# EBAZEXTV1.net
KiCad netlist of a schematic drawn in Altium Designer
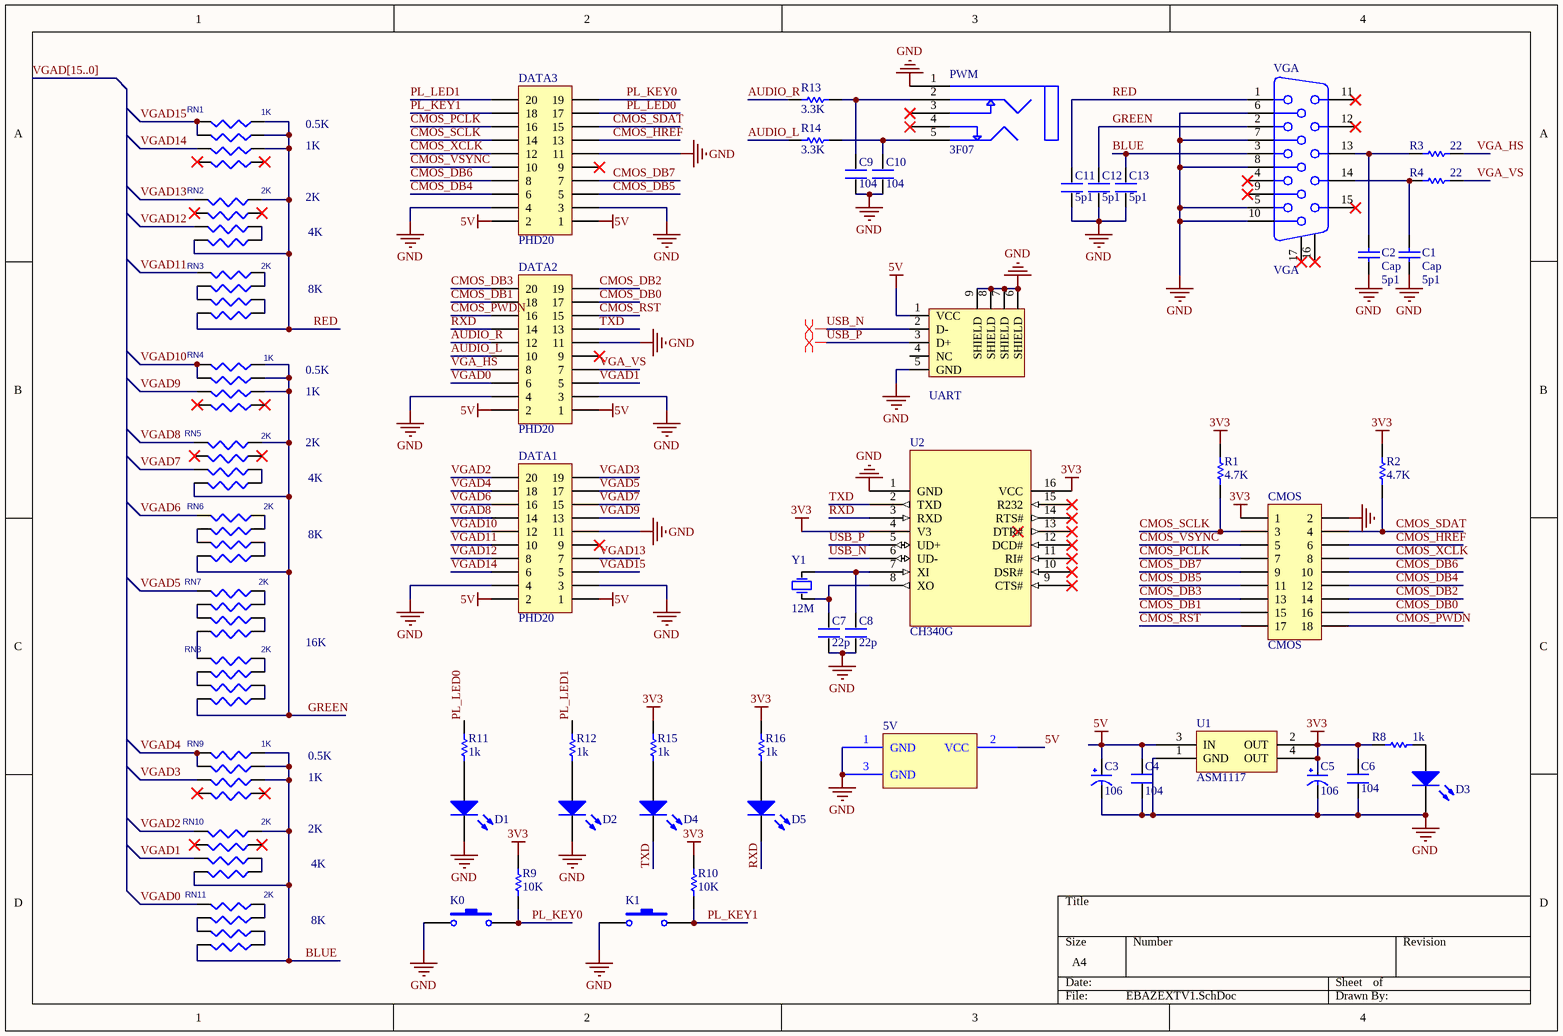
[diagram p0: EBAZEXTV1.SchDoc]

(export (version "E")
  (design (tool "Eeschema 10.0.6"))
  (components
    (comp (ref "5V")
      (value "DC005电源插座")
      (footprint "POWER_CON_max")
      (libsource (lib "FPGA+DSP") (part "POWER_CON"))
    )
    (comp (ref "C1")
      (value "Cap")
      (footprint "0805")
      (description "Capacitor")
      (fields (field (name "ALTIUM_VALUE") "5p1") (field (name "PUBLISHER") "Altium Limited"))
      (libsource (lib "Miscellaneous Devices") (part "Cap"))
    )
    (comp (ref "C2")
      (value "Cap")
      (footprint "0805")
      (description "Capacitor")
      (fields (field (name "ALTIUM_VALUE") "5p1") (field (name "PUBLISHER") "Altium Limited"))
      (libsource (lib "Miscellaneous Devices") (part "Cap"))
    )
    (comp (ref "C3") (value "106") (footprint "1206A") (libsource (lib "Explorer STM32F407封装库") (part "CAP")))
    (comp (ref "C4") (value "104") (footprint "0805") (libsource (lib "Explorer STM32F407封装库") (part "C_3")))
    (comp (ref "C5") (value "106") (footprint "1206A") (libsource (lib "Explorer STM32F407封装库") (part "CAP")))
    (comp (ref "C6") (value "104") (footprint "0805") (libsource (lib "Explorer STM32F407封装库") (part "C_3")))
    (comp (ref "C7") (value "22p") (footprint "0805") (libsource (lib "Explorer STM32F407封装库") (part "C_3")))
    (comp (ref "C8") (value "22p") (footprint "0805") (libsource (lib "Explorer STM32F407封装库") (part "C_3")))
    (comp (ref "C9") (value "104") (footprint "0805") (libsource (lib "Explorer STM32F407封装库") (part "C_3")))
    (comp (ref "C10") (value "104") (footprint "0805") (libsource (lib "Explorer STM32F407封装库") (part "C_3")))
    (comp (ref "C11") (value "5p1") (footprint "0805") (libsource (lib "Explorer STM32F407封装库") (part "C_3")))
    (comp (ref "C12") (value "5p1") (footprint "0805") (libsource (lib "Explorer STM32F407封装库") (part "C_3")))
    (comp (ref "C13") (value "5p1") (footprint "0805") (libsource (lib "Explorer STM32F407封装库") (part "C_3")))
    (comp (ref "CMOS")
      (value "CMOS")
      (footprint "HDR2X9")
      (description "Header, 9-Pin, Dual row")
      (fields (field (name "PUBLISHER") "Altium Limited"))
      (libsource (lib "Miscellaneous Connectors") (part "Header 9X2"))
    )
    (comp (ref "D1")
      (value "LED0")
      (footprint "LED-0805")
      (description "发光二极管")
      (fields (field (name "PUBLISHER") "Altium Limited"))
      (libsource (lib "fszhang") (part "LED0"))
    )
    (comp (ref "D2")
      (value "LED0")
      (footprint "LED-0805")
      (description "发光二极管")
      (fields (field (name "PUBLISHER") "Altium Limited"))
      (libsource (lib "fszhang") (part "LED0"))
    )
    (comp (ref "D3")
      (value "LED0")
      (footprint "LED-0805")
      (description "发光二极管")
      (fields (field (name "PUBLISHER") "Altium Limited"))
      (libsource (lib "fszhang") (part "LED0"))
    )
    (comp (ref "D4")
      (value "LED0")
      (footprint "LED-0805")
      (description "发光二极管")
      (fields (field (name "PUBLISHER") "Altium Limited"))
      (libsource (lib "fszhang") (part "LED0"))
    )
    (comp (ref "D5")
      (value "LED0")
      (footprint "LED-0805")
      (description "发光二极管")
      (fields (field (name "PUBLISHER") "Altium Limited"))
      (libsource (lib "fszhang") (part "LED0"))
    )
    (comp (ref "DATA1")
      (value "PHD20")
      (footprint "37")
      (description "Header, 10-Pin, Dual row")
      (fields (field (name "PUBLISHER") "Altium Limited"))
      (libsource (lib "Miscellaneous Connectors") (part "Header 10X2"))
    )
    (comp (ref "DATA2")
      (value "PHD20")
      (footprint "37")
      (description "Header, 10-Pin, Dual row")
      (fields (field (name "PUBLISHER") "Altium Limited"))
      (libsource (lib "Miscellaneous Connectors") (part "Header 10X2"))
    )
    (comp (ref "DATA3")
      (value "PHD20")
      (footprint "37")
      (description "Header, 10-Pin, Dual row")
      (fields (field (name "PUBLISHER") "Altium Limited"))
      (libsource (lib "Miscellaneous Connectors") (part "Header 10X2"))
    )
    (comp (ref "K0")
      (value "SW-PB")
      (footprint "key_2")
      (description "Switch")
      (fields (field (name "PUBLISHER") "Altium Limited"))
      (libsource (lib "Miscellaneous Devices") (part "SW-PB"))
    )
    (comp (ref "K1")
      (value "SW-PB")
      (footprint "key_2")
      (description "Switch")
      (fields (field (name "PUBLISHER") "Altium Limited"))
      (libsource (lib "Miscellaneous Devices") (part "SW-PB"))
    )
    (comp (ref "PWM")
      (value "3F07")
      (footprint "3F07")
      (description "立体声耳机插座")
      (libsource (lib "HDR_fszhang") (part "3F07"))
    )
    (comp (ref "R1")
      (value "4.7K")
      (footprint "R0805")
      (description "Resistor")
      (fields (field (name "PUBLISHER") "Altium Limited"))
      (libsource (lib "My Footprint") (part "RES"))
    )
    (comp (ref "R2")
      (value "4.7K")
      (footprint "R0805")
      (description "Resistor")
      (fields (field (name "PUBLISHER") "Altium Limited"))
      (libsource (lib "My Footprint") (part "RES"))
    )
    (comp (ref "R3")
      (value "22")
      (footprint "R0805")
      (description "Resistor")
      (fields (field (name "PUBLISHER") "Altium Limited"))
      (libsource (lib "My Footprint") (part "RES"))
    )
    (comp (ref "R4")
      (value "22")
      (footprint "R0805")
      (description "Resistor")
      (fields (field (name "PUBLISHER") "Altium Limited"))
      (libsource (lib "My Footprint") (part "RES"))
    )
    (comp (ref "R8")
      (value "1k")
      (footprint "R0805")
      (description "Resistor")
      (fields (field (name "PUBLISHER") "Altium Limited"))
      (libsource (lib "My Footprint") (part "RES"))
    )
    (comp (ref "R9")
      (value "10K")
      (footprint "R0805")
      (description "Resistor")
      (fields (field (name "PUBLISHER") "Altium Limited"))
      (libsource (lib "Miscellaneous Devices") (part "Res1"))
    )
    (comp (ref "R10")
      (value "10K")
      (footprint "R0805")
      (description "Resistor")
      (fields (field (name "PUBLISHER") "Altium Limited"))
      (libsource (lib "Miscellaneous Devices") (part "Res1"))
    )
    (comp (ref "R11")
      (value "1k")
      (footprint "R0805")
      (description "Resistor")
      (fields (field (name "PUBLISHER") "Altium Limited"))
      (libsource (lib "My Footprint") (part "RES"))
    )
    (comp (ref "R12")
      (value "1k")
      (footprint "R0805")
      (description "Resistor")
      (fields (field (name "PUBLISHER") "Altium Limited"))
      (libsource (lib "My Footprint") (part "RES"))
    )
    (comp (ref "R13")
      (value "3.3K")
      (footprint "R0805")
      (description "Resistor")
      (fields (field (name "PUBLISHER") "Altium Limited"))
      (libsource (lib "Miscellaneous Devices") (part "Res1"))
    )
    (comp (ref "R14")
      (value "3.3K")
      (footprint "R0805")
      (description "Resistor")
      (fields (field (name "PUBLISHER") "Altium Limited"))
      (libsource (lib "Miscellaneous Devices") (part "Res1"))
    )
    (comp (ref "R15")
      (value "1k")
      (footprint "R0805")
      (description "Resistor")
      (fields (field (name "PUBLISHER") "Altium Limited"))
      (libsource (lib "My Footprint") (part "RES"))
    )
    (comp (ref "R16")
      (value "1k")
      (footprint "R0805")
      (description "Resistor")
      (fields (field (name "PUBLISHER") "Altium Limited"))
      (libsource (lib "My Footprint") (part "RES"))
    )
    (comp (ref "RN1") (value "1K") (footprint "RN-8P") (libsource (lib "*") (part "RN_Dup1")))
    (comp (ref "RN2") (value "2K") (footprint "RN-8P") (libsource (lib "*") (part "RN_Dup1")))
    (comp (ref "RN3") (value "2K") (footprint "RN-8P") (libsource (lib "*") (part "RN_Dup1")))
    (comp (ref "RN4") (value "1K") (footprint "RN-8P") (libsource (lib "*") (part "RN_Dup1")))
    (comp (ref "RN5") (value "2K") (footprint "RN-8P") (libsource (lib "*") (part "RN_Dup1")))
    (comp (ref "RN6") (value "2K") (footprint "RN-8P") (libsource (lib "*") (part "RN_Dup1")))
    (comp (ref "RN7") (value "2K") (footprint "RN-8P") (libsource (lib "*") (part "RN_Dup1")))
    (comp (ref "RN8") (value "2K") (footprint "RN-8P") (libsource (lib "*") (part "RN_Dup1")))
    (comp (ref "RN9") (value "1K") (footprint "RN-8P") (libsource (lib "*") (part "RN_Dup1")))
    (comp (ref "RN10") (value "2K") (footprint "RN-8P") (libsource (lib "*") (part "RN_Dup1")))
    (comp (ref "RN11") (value "2K") (footprint "RN-8P") (libsource (lib "*") (part "RN_Dup1")))
    (comp (ref "U1")
      (value "ASM1117")
      (footprint "SOT223")
      (description "3.3V稳压芯片")
      (libsource (lib "fszhang") (part "ASM1117"))
    )
    (comp (ref "U2")
      (value "CH340G")
      (footprint "SOP16")
      (description "USB to TTL Serial / UART")
      (libsource (lib "CHXXXSCH") (part "CH340G"))
    )
    (comp (ref "UART")
      (value "USB-AB")
      (footprint "USB_AB - 5S - B")
      (description "MicroUSB")
      (libsource (lib "STM32F767核心板封装库") (part "USB-AB"))
    )
    (comp (ref "VGA")
      (value "VGA")
      (footprint "DB15-F")
      (fields (field (name "PUBLISHER") "Altium Limited"))
      (libsource (lib "HDR_fszhang") (part "D Connector 15"))
    )
    (comp (ref "Y1")
      (value "12M")
      (footprint "X-HC-49S")
      (description "晶振")
      (fields (field (name "Comment") "XTAL") (field (name "PUBLISHER") "Altium Limited"))
      (libsource (lib "fszhang") (part "XTAL"))
    )
  )
  (nets
    (net (code "1") (name "/AUDIO_L") (class "Default")
      (node (ref "DATA2") (pin "10") (pinfunction "10_10") (pintype "passive"))
      (node (ref "R14") (pin "2") (pinfunction "2_2") (pintype "passive"))
    )
    (net (code "2") (name "/AUDIO_R") (class "Default")
      (node (ref "DATA2") (pin "12") (pinfunction "12_12") (pintype "passive"))
      (node (ref "R13") (pin "1") (pinfunction "1_1") (pintype "passive"))
    )
    (net (code "3") (name "/BLUE") (class "Default")
      (node (ref "C13") (pin "2") (pintype "passive"))
      (node (ref "RN10") (pin "4") (pinfunction "4_4") (pintype "passive"))
      (node (ref "RN10") (pin "8") (pinfunction "8_8") (pintype "passive"))
      (node (ref "RN11") (pin "8") (pinfunction "8_8") (pintype "passive"))
      (node (ref "RN9") (pin "2") (pinfunction "2_2") (pintype "passive"))
      (node (ref "RN9") (pin "3") (pinfunction "3_3") (pintype "passive"))
      (node (ref "RN9") (pin "4") (pinfunction "4_4") (pintype "passive"))
      (node (ref "VGA") (pin "3") (pinfunction "3_3") (pintype "passive"))
    )
    (net (code "4") (name "/CMOS_DB0") (class "Default")
      (node (ref "CMOS") (pin "16") (pinfunction "16_16") (pintype "passive"))
      (node (ref "DATA2") (pin "17") (pinfunction "17_17") (pintype "passive"))
    )
    (net (code "5") (name "/CMOS_DB1") (class "Default")
      (node (ref "CMOS") (pin "15") (pinfunction "15_15") (pintype "passive"))
      (node (ref "DATA2") (pin "18") (pinfunction "18_18") (pintype "passive"))
    )
    (net (code "6") (name "/CMOS_DB2") (class "Default")
      (node (ref "CMOS") (pin "14") (pinfunction "14_14") (pintype "passive"))
      (node (ref "DATA2") (pin "19") (pinfunction "19_19") (pintype "passive"))
    )
    (net (code "7") (name "/CMOS_DB3") (class "Default")
      (node (ref "CMOS") (pin "13") (pinfunction "13_13") (pintype "passive"))
      (node (ref "DATA2") (pin "20") (pinfunction "20_20") (pintype "passive"))
    )
    (net (code "8") (name "/CMOS_DB4") (class "Default")
      (node (ref "CMOS") (pin "12") (pinfunction "12_12") (pintype "passive"))
      (node (ref "DATA3") (pin "6") (pinfunction "6_6") (pintype "passive"))
    )
    (net (code "9") (name "/CMOS_DB5") (class "Default")
      (node (ref "CMOS") (pin "11") (pinfunction "11_11") (pintype "passive"))
      (node (ref "DATA3") (pin "5") (pinfunction "5_5") (pintype "passive"))
    )
    (net (code "10") (name "/CMOS_DB6") (class "Default")
      (node (ref "CMOS") (pin "10") (pinfunction "10_10") (pintype "passive"))
      (node (ref "DATA3") (pin "8") (pinfunction "8_8") (pintype "passive"))
    )
    (net (code "11") (name "/CMOS_DB7") (class "Default")
      (node (ref "CMOS") (pin "9") (pinfunction "9_9") (pintype "passive"))
      (node (ref "DATA3") (pin "7") (pinfunction "7_7") (pintype "passive"))
    )
    (net (code "12") (name "/CMOS_HREF") (class "Default")
      (node (ref "CMOS") (pin "6") (pinfunction "6_6") (pintype "passive"))
      (node (ref "DATA3") (pin "13") (pinfunction "13_13") (pintype "passive"))
    )
    (net (code "13") (name "/CMOS_PCLK") (class "Default")
      (node (ref "CMOS") (pin "7") (pinfunction "7_7") (pintype "passive"))
      (node (ref "DATA3") (pin "16") (pinfunction "16_16") (pintype "passive"))
    )
    (net (code "14") (name "/CMOS_PWDN") (class "Default")
      (node (ref "CMOS") (pin "18") (pinfunction "18_18") (pintype "passive"))
      (node (ref "DATA2") (pin "16") (pinfunction "16_16") (pintype "passive"))
    )
    (net (code "15") (name "/CMOS_RST") (class "Default")
      (node (ref "CMOS") (pin "17") (pinfunction "17_17") (pintype "passive"))
      (node (ref "DATA2") (pin "15") (pinfunction "15_15") (pintype "passive"))
    )
    (net (code "16") (name "/CMOS_SCLK") (class "Default")
      (node (ref "CMOS") (pin "3") (pinfunction "3_3") (pintype "passive"))
      (node (ref "DATA3") (pin "14") (pinfunction "14_14") (pintype "passive"))
      (node (ref "R1") (pin "2") (pinfunction "2_2") (pintype "passive"))
    )
    (net (code "17") (name "/CMOS_SDAT") (class "Default")
      (node (ref "CMOS") (pin "4") (pinfunction "4_4") (pintype "passive"))
      (node (ref "DATA3") (pin "15") (pinfunction "15_15") (pintype "passive"))
      (node (ref "R2") (pin "2") (pinfunction "2_2") (pintype "passive"))
    )
    (net (code "18") (name "/CMOS_VSYNC") (class "Default")
      (node (ref "CMOS") (pin "5") (pinfunction "5_5") (pintype "passive"))
      (node (ref "DATA3") (pin "10") (pinfunction "10_10") (pintype "passive"))
    )
    (net (code "19") (name "/CMOS_XCLK") (class "Default")
      (node (ref "CMOS") (pin "8") (pinfunction "8_8") (pintype "passive"))
      (node (ref "DATA3") (pin "12") (pinfunction "12_12") (pintype "passive"))
    )
    (net (code "20") (name "/GREEN") (class "Default")
      (node (ref "C12") (pin "2") (pintype "passive"))
      (node (ref "RN4") (pin "2") (pinfunction "2_2") (pintype "passive"))
      (node (ref "RN4") (pin "3") (pinfunction "3_3") (pintype "passive"))
      (node (ref "RN4") (pin "4") (pinfunction "4_4") (pintype "passive"))
      (node (ref "RN5") (pin "4") (pinfunction "4_4") (pintype "passive"))
      (node (ref "RN5") (pin "8") (pinfunction "8_8") (pintype "passive"))
      (node (ref "RN6") (pin "8") (pinfunction "8_8") (pintype "passive"))
      (node (ref "RN8") (pin "8") (pinfunction "8_8") (pintype "passive"))
      (node (ref "VGA") (pin "2") (pinfunction "2_2") (pintype "passive"))
    )
    (net (code "21") (name "/PL_KEY0") (class "Default")
      (node (ref "DATA3") (pin "19") (pinfunction "19_19") (pintype "passive"))
      (node (ref "K0") (pin "2") (pinfunction "2_2") (pintype "passive"))
      (node (ref "R9") (pin "1") (pinfunction "1_1") (pintype "passive"))
    )
    (net (code "22") (name "/PL_KEY1") (class "Default")
      (node (ref "DATA3") (pin "18") (pinfunction "18_18") (pintype "passive"))
      (node (ref "K1") (pin "2") (pinfunction "2_2") (pintype "passive"))
      (node (ref "R10") (pin "1") (pinfunction "1_1") (pintype "passive"))
    )
    (net (code "23") (name "/PL_LED0") (class "Default")
      (node (ref "DATA3") (pin "17") (pinfunction "17_17") (pintype "passive"))
      (node (ref "R11") (pin "1") (pinfunction "1_1") (pintype "passive"))
    )
    (net (code "24") (name "/PL_LED1") (class "Default")
      (node (ref "DATA3") (pin "20") (pinfunction "20_20") (pintype "passive"))
      (node (ref "R12") (pin "1") (pinfunction "1_1") (pintype "passive"))
    )
    (net (code "25") (name "/RED") (class "Default")
      (node (ref "C11") (pin "2") (pintype "passive"))
      (node (ref "RN1") (pin "2") (pinfunction "2_2") (pintype "passive"))
      (node (ref "RN1") (pin "3") (pinfunction "3_3") (pintype "passive"))
      (node (ref "RN1") (pin "4") (pinfunction "4_4") (pintype "passive"))
      (node (ref "RN2") (pin "4") (pinfunction "4_4") (pintype "passive"))
      (node (ref "RN2") (pin "8") (pinfunction "8_8") (pintype "passive"))
      (node (ref "RN3") (pin "8") (pinfunction "8_8") (pintype "passive"))
      (node (ref "VGA") (pin "1") (pinfunction "1_1") (pintype "passive"))
    )
    (net (code "26") (name "/RXD") (class "Default")
      (node (ref "D5") (pin "2") (pinfunction "K_2") (pintype "passive"))
      (node (ref "DATA2") (pin "14") (pinfunction "14_14") (pintype "passive"))
      (node (ref "U2") (pin "3") (pinfunction "RXD_3") (pintype "input"))
    )
    (net (code "27") (name "/TXD") (class "Default")
      (node (ref "D4") (pin "2") (pinfunction "K_2") (pintype "passive"))
      (node (ref "DATA2") (pin "13") (pinfunction "13_13") (pintype "passive"))
      (node (ref "U2") (pin "2") (pinfunction "TXD_2") (pintype "output"))
    )
    (net (code "28") (name "/USB_N") (class "Default")
      (node (ref "U2") (pin "6") (pinfunction "UD-_6") (pintype "bidirectional"))
      (node (ref "UART") (pin "2") (pinfunction "D-_2") (pintype "passive"))
    )
    (net (code "29") (name "/USB_P") (class "Default")
      (node (ref "U2") (pin "5") (pinfunction "UD+_5") (pintype "bidirectional"))
      (node (ref "UART") (pin "3") (pinfunction "D+_3") (pintype "passive"))
    )
    (net (code "30") (name "/VGAD0") (class "Default")
      (node (ref "DATA2") (pin "6") (pinfunction "6_6") (pintype "passive"))
      (node (ref "RN11") (pin "5") (pinfunction "5_5") (pintype "passive"))
    )
    (net (code "31") (name "/VGAD1") (class "Default")
      (node (ref "DATA2") (pin "5") (pinfunction "5_5") (pintype "passive"))
      (node (ref "RN10") (pin "7") (pinfunction "7_7") (pintype "passive"))
    )
    (net (code "32") (name "/VGAD2") (class "Default")
      (node (ref "DATA1") (pin "20") (pinfunction "20_20") (pintype "passive"))
      (node (ref "RN10") (pin "5") (pinfunction "5_5") (pintype "passive"))
    )
    (net (code "33") (name "/VGAD3") (class "Default")
      (node (ref "DATA1") (pin "19") (pinfunction "19_19") (pintype "passive"))
      (node (ref "RN9") (pin "7") (pinfunction "7_7") (pintype "passive"))
    )
    (net (code "34") (name "/VGAD4") (class "Default")
      (node (ref "DATA1") (pin "18") (pinfunction "18_18") (pintype "passive"))
      (node (ref "RN9") (pin "5") (pinfunction "5_5") (pintype "passive"))
      (node (ref "RN9") (pin "6") (pinfunction "6_6") (pintype "passive"))
    )
    (net (code "35") (name "/VGAD5") (class "Default")
      (node (ref "DATA1") (pin "17") (pinfunction "17_17") (pintype "passive"))
      (node (ref "RN7") (pin "5") (pinfunction "5_5") (pintype "passive"))
    )
    (net (code "36") (name "/VGAD6") (class "Default")
      (node (ref "DATA1") (pin "16") (pinfunction "16_16") (pintype "passive"))
      (node (ref "RN6") (pin "5") (pinfunction "5_5") (pintype "passive"))
    )
    (net (code "37") (name "/VGAD7") (class "Default")
      (node (ref "DATA1") (pin "15") (pinfunction "15_15") (pintype "passive"))
      (node (ref "RN5") (pin "7") (pinfunction "7_7") (pintype "passive"))
    )
    (net (code "38") (name "/VGAD8") (class "Default")
      (node (ref "DATA1") (pin "14") (pinfunction "14_14") (pintype "passive"))
      (node (ref "RN5") (pin "5") (pinfunction "5_5") (pintype "passive"))
    )
    (net (code "39") (name "/VGAD9") (class "Default")
      (node (ref "DATA1") (pin "13") (pinfunction "13_13") (pintype "passive"))
      (node (ref "RN4") (pin "7") (pinfunction "7_7") (pintype "passive"))
    )
    (net (code "40") (name "/VGAD10") (class "Default")
      (node (ref "DATA1") (pin "12") (pinfunction "12_12") (pintype "passive"))
      (node (ref "RN4") (pin "5") (pinfunction "5_5") (pintype "passive"))
      (node (ref "RN4") (pin "6") (pinfunction "6_6") (pintype "passive"))
    )
    (net (code "41") (name "/VGAD11") (class "Default")
      (node (ref "DATA1") (pin "10") (pinfunction "10_10") (pintype "passive"))
      (node (ref "RN3") (pin "5") (pinfunction "5_5") (pintype "passive"))
    )
    (net (code "42") (name "/VGAD12") (class "Default")
      (node (ref "DATA1") (pin "8") (pinfunction "8_8") (pintype "passive"))
      (node (ref "RN2") (pin "7") (pinfunction "7_7") (pintype "passive"))
    )
    (net (code "43") (name "/VGAD13") (class "Default")
      (node (ref "DATA1") (pin "7") (pinfunction "7_7") (pintype "passive"))
      (node (ref "RN2") (pin "5") (pinfunction "5_5") (pintype "passive"))
    )
    (net (code "44") (name "/VGAD14") (class "Default")
      (node (ref "DATA1") (pin "6") (pinfunction "6_6") (pintype "passive"))
      (node (ref "RN1") (pin "7") (pinfunction "7_7") (pintype "passive"))
    )
    (net (code "45") (name "/VGAD15") (class "Default")
      (node (ref "DATA1") (pin "5") (pinfunction "5_5") (pintype "passive"))
      (node (ref "RN1") (pin "5") (pinfunction "5_5") (pintype "passive"))
      (node (ref "RN1") (pin "6") (pinfunction "6_6") (pintype "passive"))
    )
    (net (code "47") (name "/VGA_HS") (class "Default")
      (node (ref "DATA2") (pin "8") (pinfunction "8_8") (pintype "passive"))
      (node (ref "R3") (pin "1") (pinfunction "1_1") (pintype "passive"))
    )
    (net (code "48") (name "/VGA_VS") (class "Default")
      (node (ref "DATA2") (pin "7") (pinfunction "7_7") (pintype "passive"))
      (node (ref "R4") (pin "1") (pinfunction "1_1") (pintype "passive"))
    )
    (net (code "49") (name "3V3") (class "Default")
      (node (ref "C5") (pin "1") (pinfunction "VCC_1") (pintype "passive"))
      (node (ref "C6") (pin "2") (pintype "passive"))
      (node (ref "CMOS") (pin "1") (pinfunction "1_1") (pintype "passive"))
      (node (ref "R1") (pin "1") (pinfunction "1_1") (pintype "passive"))
      (node (ref "R10") (pin "2") (pinfunction "2_2") (pintype "passive"))
      (node (ref "R15") (pin "1") (pinfunction "1_1") (pintype "passive"))
      (node (ref "R16") (pin "1") (pinfunction "1_1") (pintype "passive"))
      (node (ref "R2") (pin "1") (pinfunction "1_1") (pintype "passive"))
      (node (ref "R8") (pin "2") (pinfunction "2_2") (pintype "passive"))
      (node (ref "R9") (pin "2") (pinfunction "2_2") (pintype "passive"))
      (node (ref "U1") (pin "2") (pinfunction "OUT_2") (pintype "passive"))
      (node (ref "U1") (pin "4") (pinfunction "OUT_4") (pintype "passive"))
      (node (ref "U2") (pin "16") (pinfunction "VCC_16") (pintype "power_in"))
      (node (ref "U2") (pin "4") (pinfunction "V3_4") (pintype "power_in"))
    )
    (net (code "50") (name "5V") (class "Default")
      (node (ref "5V") (pin "2") (pinfunction "VCC_2") (pintype "passive"))
      (node (ref "C3") (pin "1") (pinfunction "VCC_1") (pintype "passive"))
      (node (ref "C4") (pin "2") (pintype "passive"))
      (node (ref "DATA1") (pin "1") (pinfunction "1_1") (pintype "passive"))
      (node (ref "DATA1") (pin "2") (pinfunction "2_2") (pintype "passive"))
      (node (ref "DATA2") (pin "1") (pinfunction "1_1") (pintype "passive"))
      (node (ref "DATA2") (pin "2") (pinfunction "2_2") (pintype "passive"))
      (node (ref "DATA3") (pin "1") (pinfunction "1_1") (pintype "passive"))
      (node (ref "DATA3") (pin "2") (pinfunction "2_2") (pintype "passive"))
      (node (ref "U1") (pin "3") (pinfunction "IN_3") (pintype "passive"))
      (node (ref "UART") (pin "1") (pinfunction "VCC_1") (pintype "passive"))
    )
    (net (code "51") (name "GND") (class "Default")
      (node (ref "5V") (pin "1") (pinfunction "GND_1") (pintype "passive"))
      (node (ref "5V") (pin "3") (pinfunction "GND_3") (pintype "passive"))
      (node (ref "C1") (pin "1") (pinfunction "1_1") (pintype "passive"))
      (node (ref "C10") (pin "1") (pintype "passive"))
      (node (ref "C11") (pin "1") (pintype "passive"))
      (node (ref "C12") (pin "1") (pintype "passive"))
      (node (ref "C13") (pin "1") (pintype "passive"))
      (node (ref "C2") (pin "1") (pinfunction "1_1") (pintype "passive"))
      (node (ref "C3") (pin "2") (pinfunction "GND_2") (pintype "passive"))
      (node (ref "C4") (pin "1") (pintype "passive"))
      (node (ref "C5") (pin "2") (pinfunction "GND_2") (pintype "passive"))
      (node (ref "C6") (pin "1") (pintype "passive"))
      (node (ref "C7") (pin "1") (pintype "passive"))
      (node (ref "C8") (pin "1") (pintype "passive"))
      (node (ref "C9") (pin "1") (pintype "passive"))
      (node (ref "CMOS") (pin "2") (pinfunction "2_2") (pintype "passive"))
      (node (ref "D1") (pin "2") (pinfunction "K_2") (pintype "passive"))
      (node (ref "D2") (pin "2") (pinfunction "K_2") (pintype "passive"))
      (node (ref "D3") (pin "2") (pinfunction "K_2") (pintype "passive"))
      (node (ref "DATA1") (pin "11") (pinfunction "11_11") (pintype "passive"))
      (node (ref "DATA1") (pin "3") (pinfunction "3_3") (pintype "passive"))
      (node (ref "DATA1") (pin "4") (pinfunction "4_4") (pintype "passive"))
      (node (ref "DATA2") (pin "11") (pinfunction "11_11") (pintype "passive"))
      (node (ref "DATA2") (pin "3") (pinfunction "3_3") (pintype "passive"))
      (node (ref "DATA2") (pin "4") (pinfunction "4_4") (pintype "passive"))
      (node (ref "DATA3") (pin "11") (pinfunction "11_11") (pintype "passive"))
      (node (ref "DATA3") (pin "3") (pinfunction "3_3") (pintype "passive"))
      (node (ref "DATA3") (pin "4") (pinfunction "4_4") (pintype "passive"))
      (node (ref "K0") (pin "1") (pinfunction "1_1") (pintype "passive"))
      (node (ref "K1") (pin "1") (pinfunction "1_1") (pintype "passive"))
      (node (ref "PWM") (pin "1") (pinfunction "COM_1") (pintype "passive"))
      (node (ref "U1") (pin "1") (pinfunction "GND_1") (pintype "passive"))
      (node (ref "U2") (pin "1") (pinfunction "GND_1") (pintype "power_in"))
      (node (ref "UART") (pin "5") (pinfunction "GND_5") (pintype "passive"))
      (node (ref "UART") (pin "6") (pinfunction "SHIELD_6") (pintype "passive"))
      (node (ref "UART") (pin "7") (pinfunction "SHIELD_7") (pintype "passive"))
      (node (ref "UART") (pin "8") (pinfunction "SHIELD_8") (pintype "passive"))
      (node (ref "UART") (pin "9") (pinfunction "SHIELD_9") (pintype "passive"))
      (node (ref "VGA") (pin "10") (pinfunction "10_10") (pintype "passive"))
      (node (ref "VGA") (pin "5") (pinfunction "5_5") (pintype "passive"))
      (node (ref "VGA") (pin "6") (pinfunction "6_6") (pintype "passive"))
      (node (ref "VGA") (pin "7") (pinfunction "7_7") (pintype "passive"))
      (node (ref "VGA") (pin "8") (pinfunction "8_8") (pintype "passive"))
    )
    (net (code "52") (name "Net-(C1-Pad2)") (class "Default")
      (node (ref "C1") (pin "2") (pinfunction "2_2") (pintype "passive"))
      (node (ref "R4") (pin "2") (pinfunction "2_2") (pintype "passive"))
      (node (ref "VGA") (pin "14") (pinfunction "14_14") (pintype "passive"))
    )
    (net (code "53") (name "Net-(C2-Pad2)") (class "Default")
      (node (ref "C2") (pin "2") (pinfunction "2_2") (pintype "passive"))
      (node (ref "R3") (pin "2") (pinfunction "2_2") (pintype "passive"))
      (node (ref "VGA") (pin "13") (pinfunction "13_13") (pintype "passive"))
    )
    (net (code "54") (name "Net-(D1-A)") (class "Default")
      (node (ref "D1") (pin "1") (pinfunction "A_1") (pintype "passive"))
      (node (ref "R11") (pin "2") (pinfunction "2_2") (pintype "passive"))
    )
    (net (code "55") (name "Net-(D2-A)") (class "Default")
      (node (ref "D2") (pin "1") (pinfunction "A_1") (pintype "passive"))
      (node (ref "R12") (pin "2") (pinfunction "2_2") (pintype "passive"))
    )
    (net (code "56") (name "Net-(D3-A)") (class "Default")
      (node (ref "D3") (pin "1") (pinfunction "A_1") (pintype "passive"))
      (node (ref "R8") (pin "1") (pinfunction "1_1") (pintype "passive"))
    )
    (net (code "57") (name "Net-(D4-A)") (class "Default")
      (node (ref "D4") (pin "1") (pinfunction "A_1") (pintype "passive"))
      (node (ref "R15") (pin "2") (pinfunction "2_2") (pintype "passive"))
    )
    (net (code "58") (name "Net-(D5-A)") (class "Default")
      (node (ref "D5") (pin "1") (pinfunction "A_1") (pintype "passive"))
      (node (ref "R16") (pin "2") (pinfunction "2_2") (pintype "passive"))
    )
    (net (code "59") (name "Net-(PWM-L1)") (class "Default")
      (node (ref "C10") (pin "2") (pintype "passive"))
      (node (ref "PWM") (pin "5") (pinfunction "L1_5") (pintype "passive"))
      (node (ref "R14") (pin "1") (pinfunction "1_1") (pintype "passive"))
    )
    (net (code "60") (name "Net-(PWM-R1)") (class "Default")
      (node (ref "C9") (pin "2") (pintype "passive"))
      (node (ref "PWM") (pin "2") (pinfunction "R1_2") (pintype "passive"))
      (node (ref "R13") (pin "2") (pinfunction "2_2") (pintype "passive"))
    )
    (net (code "61") (name "Net-(RN2-Pad1)") (class "Default")
      (node (ref "RN2") (pin "1") (pinfunction "1_1") (pintype "passive"))
      (node (ref "RN2") (pin "2") (pinfunction "2_2") (pintype "passive"))
    )
    (net (code "62") (name "Net-(RN3-Pad1)") (class "Default")
      (node (ref "RN3") (pin "1") (pinfunction "1_1") (pintype "passive"))
      (node (ref "RN3") (pin "2") (pinfunction "2_2") (pintype "passive"))
    )
    (net (code "63") (name "Net-(RN3-Pad3)") (class "Default")
      (node (ref "RN3") (pin "3") (pinfunction "3_3") (pintype "passive"))
      (node (ref "RN3") (pin "4") (pinfunction "4_4") (pintype "passive"))
    )
    (net (code "64") (name "Net-(RN3-Pad6)") (class "Default")
      (node (ref "RN3") (pin "6") (pinfunction "6_6") (pintype "passive"))
      (node (ref "RN3") (pin "7") (pinfunction "7_7") (pintype "passive"))
    )
    (net (code "65") (name "Net-(RN5-Pad1)") (class "Default")
      (node (ref "RN5") (pin "1") (pinfunction "1_1") (pintype "passive"))
      (node (ref "RN5") (pin "2") (pinfunction "2_2") (pintype "passive"))
    )
    (net (code "66") (name "Net-(RN6-Pad1)") (class "Default")
      (node (ref "RN6") (pin "1") (pinfunction "1_1") (pintype "passive"))
      (node (ref "RN6") (pin "2") (pinfunction "2_2") (pintype "passive"))
    )
    (net (code "67") (name "Net-(RN6-Pad3)") (class "Default")
      (node (ref "RN6") (pin "3") (pinfunction "3_3") (pintype "passive"))
      (node (ref "RN6") (pin "4") (pinfunction "4_4") (pintype "passive"))
    )
    (net (code "68") (name "Net-(RN6-Pad6)") (class "Default")
      (node (ref "RN6") (pin "6") (pinfunction "6_6") (pintype "passive"))
      (node (ref "RN6") (pin "7") (pinfunction "7_7") (pintype "passive"))
    )
    (net (code "69") (name "Net-(RN7-Pad1)") (class "Default")
      (node (ref "RN7") (pin "1") (pinfunction "1_1") (pintype "passive"))
      (node (ref "RN7") (pin "2") (pinfunction "2_2") (pintype "passive"))
    )
    (net (code "70") (name "Net-(RN7-Pad3)") (class "Default")
      (node (ref "RN7") (pin "3") (pinfunction "3_3") (pintype "passive"))
      (node (ref "RN7") (pin "4") (pinfunction "4_4") (pintype "passive"))
    )
    (net (code "71") (name "Net-(RN7-Pad6)") (class "Default")
      (node (ref "RN7") (pin "6") (pinfunction "6_6") (pintype "passive"))
      (node (ref "RN7") (pin "7") (pinfunction "7_7") (pintype "passive"))
    )
    (net (code "72") (name "Net-(RN7-Pad8)") (class "Default")
      (node (ref "RN7") (pin "8") (pinfunction "8_8") (pintype "passive"))
      (node (ref "RN8") (pin "5") (pinfunction "5_5") (pintype "passive"))
    )
    (net (code "73") (name "Net-(RN8-Pad1)") (class "Default")
      (node (ref "RN8") (pin "1") (pinfunction "1_1") (pintype "passive"))
      (node (ref "RN8") (pin "2") (pinfunction "2_2") (pintype "passive"))
    )
    (net (code "74") (name "Net-(RN8-Pad3)") (class "Default")
      (node (ref "RN8") (pin "3") (pinfunction "3_3") (pintype "passive"))
      (node (ref "RN8") (pin "4") (pinfunction "4_4") (pintype "passive"))
    )
    (net (code "75") (name "Net-(RN8-Pad6)") (class "Default")
      (node (ref "RN8") (pin "6") (pinfunction "6_6") (pintype "passive"))
      (node (ref "RN8") (pin "7") (pinfunction "7_7") (pintype "passive"))
    )
    (net (code "76") (name "Net-(RN10-Pad1)") (class "Default")
      (node (ref "RN10") (pin "1") (pinfunction "1_1") (pintype "passive"))
      (node (ref "RN10") (pin "2") (pinfunction "2_2") (pintype "passive"))
    )
    (net (code "77") (name "Net-(RN11-Pad1)") (class "Default")
      (node (ref "RN11") (pin "1") (pinfunction "1_1") (pintype "passive"))
      (node (ref "RN11") (pin "2") (pinfunction "2_2") (pintype "passive"))
    )
    (net (code "78") (name "Net-(RN11-Pad3)") (class "Default")
      (node (ref "RN11") (pin "3") (pinfunction "3_3") (pintype "passive"))
      (node (ref "RN11") (pin "4") (pinfunction "4_4") (pintype "passive"))
    )
    (net (code "79") (name "Net-(RN11-Pad6)") (class "Default")
      (node (ref "RN11") (pin "6") (pinfunction "6_6") (pintype "passive"))
      (node (ref "RN11") (pin "7") (pinfunction "7_7") (pintype "passive"))
    )
    (net (code "80") (name "Net-(U2-XI)") (class "Default")
      (node (ref "C8") (pin "2") (pintype "passive"))
      (node (ref "U2") (pin "7") (pinfunction "XI_7") (pintype "input"))
      (node (ref "Y1") (pin "2") (pinfunction "OSC2_2") (pintype "passive"))
    )
    (net (code "81") (name "Net-(U2-XO)") (class "Default")
      (node (ref "C7") (pin "2") (pintype "passive"))
      (node (ref "U2") (pin "8") (pinfunction "XO_8") (pintype "output"))
      (node (ref "Y1") (pin "1") (pinfunction "OSC1_1") (pintype "passive"))
    )
    (net (code "82") (name "unconnected-(DATA1-Pad9)") (class "Default")
      (node (ref "DATA1") (pin "9") (pinfunction "9_9") (pintype "passive+no_connect"))
    )
    (net (code "83") (name "unconnected-(DATA2-Pad9)") (class "Default")
      (node (ref "DATA2") (pin "9") (pinfunction "9_9") (pintype "passive+no_connect"))
    )
    (net (code "84") (name "unconnected-(DATA3-Pad9)") (class "Default")
      (node (ref "DATA3") (pin "9") (pinfunction "9_9") (pintype "passive+no_connect"))
    )
    (net (code "85") (name "unconnected-(PWM-L2-Pad4)") (class "Default")
      (node (ref "PWM") (pin "4") (pinfunction "L2_4") (pintype "passive+no_connect"))
    )
    (net (code "86") (name "unconnected-(PWM-R2-Pad3)") (class "Default")
      (node (ref "PWM") (pin "3") (pinfunction "R2_3") (pintype "passive+no_connect"))
    )
    (net (code "87") (name "unconnected-(RN1-Pad1)") (class "Default")
      (node (ref "RN1") (pin "1") (pinfunction "1_1") (pintype "passive+no_connect"))
    )
    (net (code "88") (name "unconnected-(RN1-Pad8)") (class "Default")
      (node (ref "RN1") (pin "8") (pinfunction "8_8") (pintype "passive+no_connect"))
    )
    (net (code "89") (name "unconnected-(RN2-Pad3)") (class "Default")
      (node (ref "RN2") (pin "3") (pinfunction "3_3") (pintype "passive+no_connect"))
    )
    (net (code "90") (name "unconnected-(RN2-Pad6)") (class "Default")
      (node (ref "RN2") (pin "6") (pinfunction "6_6") (pintype "passive+no_connect"))
    )
    (net (code "91") (name "unconnected-(RN4-Pad1)") (class "Default")
      (node (ref "RN4") (pin "1") (pinfunction "1_1") (pintype "passive+no_connect"))
    )
    (net (code "92") (name "unconnected-(RN4-Pad8)") (class "Default")
      (node (ref "RN4") (pin "8") (pinfunction "8_8") (pintype "passive+no_connect"))
    )
    (net (code "93") (name "unconnected-(RN5-Pad3)") (class "Default")
      (node (ref "RN5") (pin "3") (pinfunction "3_3") (pintype "passive+no_connect"))
    )
    (net (code "94") (name "unconnected-(RN5-Pad6)") (class "Default")
      (node (ref "RN5") (pin "6") (pinfunction "6_6") (pintype "passive+no_connect"))
    )
    (net (code "95") (name "unconnected-(RN9-Pad1)") (class "Default")
      (node (ref "RN9") (pin "1") (pinfunction "1_1") (pintype "passive+no_connect"))
    )
    (net (code "96") (name "unconnected-(RN9-Pad8)") (class "Default")
      (node (ref "RN9") (pin "8") (pinfunction "8_8") (pintype "passive+no_connect"))
    )
    (net (code "97") (name "unconnected-(RN10-Pad3)") (class "Default")
      (node (ref "RN10") (pin "3") (pinfunction "3_3") (pintype "passive+no_connect"))
    )
    (net (code "98") (name "unconnected-(RN10-Pad6)") (class "Default")
      (node (ref "RN10") (pin "6") (pinfunction "6_6") (pintype "passive+no_connect"))
    )
    (net (code "99") (name "unconnected-(U2-CTS#-Pad9)") (class "Default")
      (node (ref "U2") (pin "9") (pinfunction "CTS#_9") (pintype "input+no_connect"))
    )
    (net (code "100") (name "unconnected-(U2-DCD#-Pad12)") (class "Default")
      (node (ref "U2") (pin "12") (pinfunction "DCD#_12") (pintype "input+no_connect"))
    )
    (net (code "101") (name "unconnected-(U2-DSR#-Pad10)") (class "Default")
      (node (ref "U2") (pin "10") (pinfunction "DSR#_10") (pintype "input+no_connect"))
    )
    (net (code "102") (name "unconnected-(U2-DTR#-Pad13)") (class "Default")
      (node (ref "U2") (pin "13") (pinfunction "DTR#_13") (pintype "output+no_connect"))
    )
    (net (code "103") (name "unconnected-(U2-R232-Pad15)") (class "Default")
      (node (ref "U2") (pin "15") (pinfunction "R232_15") (pintype "input+no_connect"))
    )
    (net (code "104") (name "unconnected-(U2-RI#-Pad11)") (class "Default")
      (node (ref "U2") (pin "11") (pinfunction "RI#_11") (pintype "input+no_connect"))
    )
    (net (code "105") (name "unconnected-(U2-RTS#-Pad14)") (class "Default")
      (node (ref "U2") (pin "14") (pinfunction "RTS#_14") (pintype "output+no_connect"))
    )
    (net (code "106") (name "unconnected-(UART-NC-Pad4)") (class "Default")
      (node (ref "UART") (pin "4") (pinfunction "NC_4") (pintype "passive"))
    )
    (net (code "107") (name "unconnected-(VGA-MH1-Pad17)") (class "Default")
      (node (ref "VGA") (pin "17") (pinfunction "MH1_17") (pintype "passive+no_connect"))
    )
    (net (code "108") (name "unconnected-(VGA-MH2-Pad16)") (class "Default")
      (node (ref "VGA") (pin "16") (pinfunction "MH2_16") (pintype "passive+no_connect"))
    )
    (net (code "109") (name "unconnected-(VGA-Pad4)") (class "Default")
      (node (ref "VGA") (pin "4") (pinfunction "4_4") (pintype "passive+no_connect"))
    )
    (net (code "110") (name "unconnected-(VGA-Pad9)") (class "Default")
      (node (ref "VGA") (pin "9") (pinfunction "9_9") (pintype "passive+no_connect"))
    )
    (net (code "111") (name "unconnected-(VGA-Pad11)") (class "Default")
      (node (ref "VGA") (pin "11") (pinfunction "11_11") (pintype "passive+no_connect"))
    )
    (net (code "112") (name "unconnected-(VGA-Pad12)") (class "Default")
      (node (ref "VGA") (pin "12") (pinfunction "12_12") (pintype "passive+no_connect"))
    )
    (net (code "113") (name "unconnected-(VGA-Pad15)") (class "Default")
      (node (ref "VGA") (pin "15") (pinfunction "15_15") (pintype "passive+no_connect"))
    )
  )
)
